# DS_PLUS.net
KiCad netlist of a schematic drawn in EAGLE
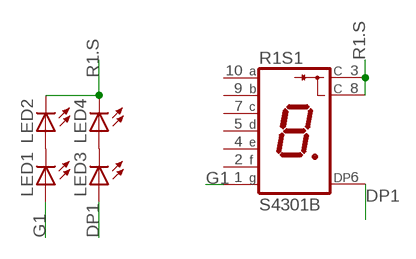
[diagram p0: schematic, sheet 1]

(export (version "E")
  (design (tool "Eeschema 10.0.6"))
  (components
    (comp (ref "LED1")
      (value "LEDCHIP-LED0603")
      (footprint "eagle-import:CHIP-LED0603")
      (libsource (lib "eagle-import") (part "LEDCHIP-LED0603"))
    )
    (comp (ref "LED2")
      (value "LEDCHIP-LED0603")
      (footprint "eagle-import:CHIP-LED0603")
      (libsource (lib "eagle-import") (part "LEDCHIP-LED0603"))
    )
    (comp (ref "LED3")
      (value "LEDCHIP-LED0603")
      (footprint "eagle-import:CHIP-LED0603")
      (libsource (lib "eagle-import") (part "LEDCHIP-LED0603"))
    )
    (comp (ref "LED4")
      (value "LEDCHIP-LED0603")
      (footprint "eagle-import:CHIP-LED0603")
      (libsource (lib "eagle-import") (part "LEDCHIP-LED0603"))
    )
    (comp (ref "R1S1")
      (value "S4301B")
      (footprint "eagle-import:S4301B")
      (libsource (lib "eagle-import") (part "S4301B"))
    )
  )
  (nets
    (net (code "1") (name "/DP1") (class "Default")
      (node (ref "LED3") (pin "A") (pinfunction "A_A") (pintype "passive"))
      (node (ref "R1S1") (pin "6") (pinfunction "DP_6") (pintype "passive"))
    )
    (net (code "2") (name "/G1") (class "Default")
      (node (ref "LED1") (pin "A") (pinfunction "A_A") (pintype "passive"))
      (node (ref "R1S1") (pin "1") (pinfunction "G_1") (pintype "passive"))
    )
    (net (code "3") (name "/R1.S") (class "Default")
      (node (ref "LED2") (pin "C") (pinfunction "C_C") (pintype "passive"))
      (node (ref "LED4") (pin "C") (pinfunction "C_C") (pintype "passive"))
      (node (ref "R1S1") (pin "3") (pinfunction "C_3") (pintype "passive"))
      (node (ref "R1S1") (pin "8") (pinfunction "C_8") (pintype "passive"))
    )
    (net (code "4") (name "Net-(LED1-PadC)") (class "Default")
      (node (ref "LED1") (pin "C") (pinfunction "C_C") (pintype "passive"))
      (node (ref "LED2") (pin "A") (pinfunction "A_A") (pintype "passive"))
    )
    (net (code "5") (name "Net-(LED3-PadC)") (class "Default")
      (node (ref "LED3") (pin "C") (pinfunction "C_C") (pintype "passive"))
      (node (ref "LED4") (pin "A") (pinfunction "A_A") (pintype "passive"))
    )
    (net (code "6") (name "unconnected-(R1S1-A-Pad10)") (class "Default")
      (node (ref "R1S1") (pin "10") (pinfunction "A_10") (pintype "passive"))
    )
    (net (code "7") (name "unconnected-(R1S1-B-Pad9)") (class "Default")
      (node (ref "R1S1") (pin "9") (pinfunction "B_9") (pintype "passive"))
    )
    (net (code "8") (name "unconnected-(R1S1-C-Pad7)") (class "Default")
      (node (ref "R1S1") (pin "7") (pinfunction "C_7") (pintype "passive"))
    )
    (net (code "9") (name "unconnected-(R1S1-D-Pad5)") (class "Default")
      (node (ref "R1S1") (pin "5") (pinfunction "D_5") (pintype "passive"))
    )
    (net (code "10") (name "unconnected-(R1S1-E-Pad4)") (class "Default")
      (node (ref "R1S1") (pin "4") (pinfunction "E_4") (pintype "passive"))
    )
    (net (code "11") (name "unconnected-(R1S1-F-Pad2)") (class "Default")
      (node (ref "R1S1") (pin "2") (pinfunction "F_2") (pintype "passive"))
    )
  )
)
